# SCH_SrProj_v1_6_final.net
KiCad netlist of a schematic drawn in EasyEDA
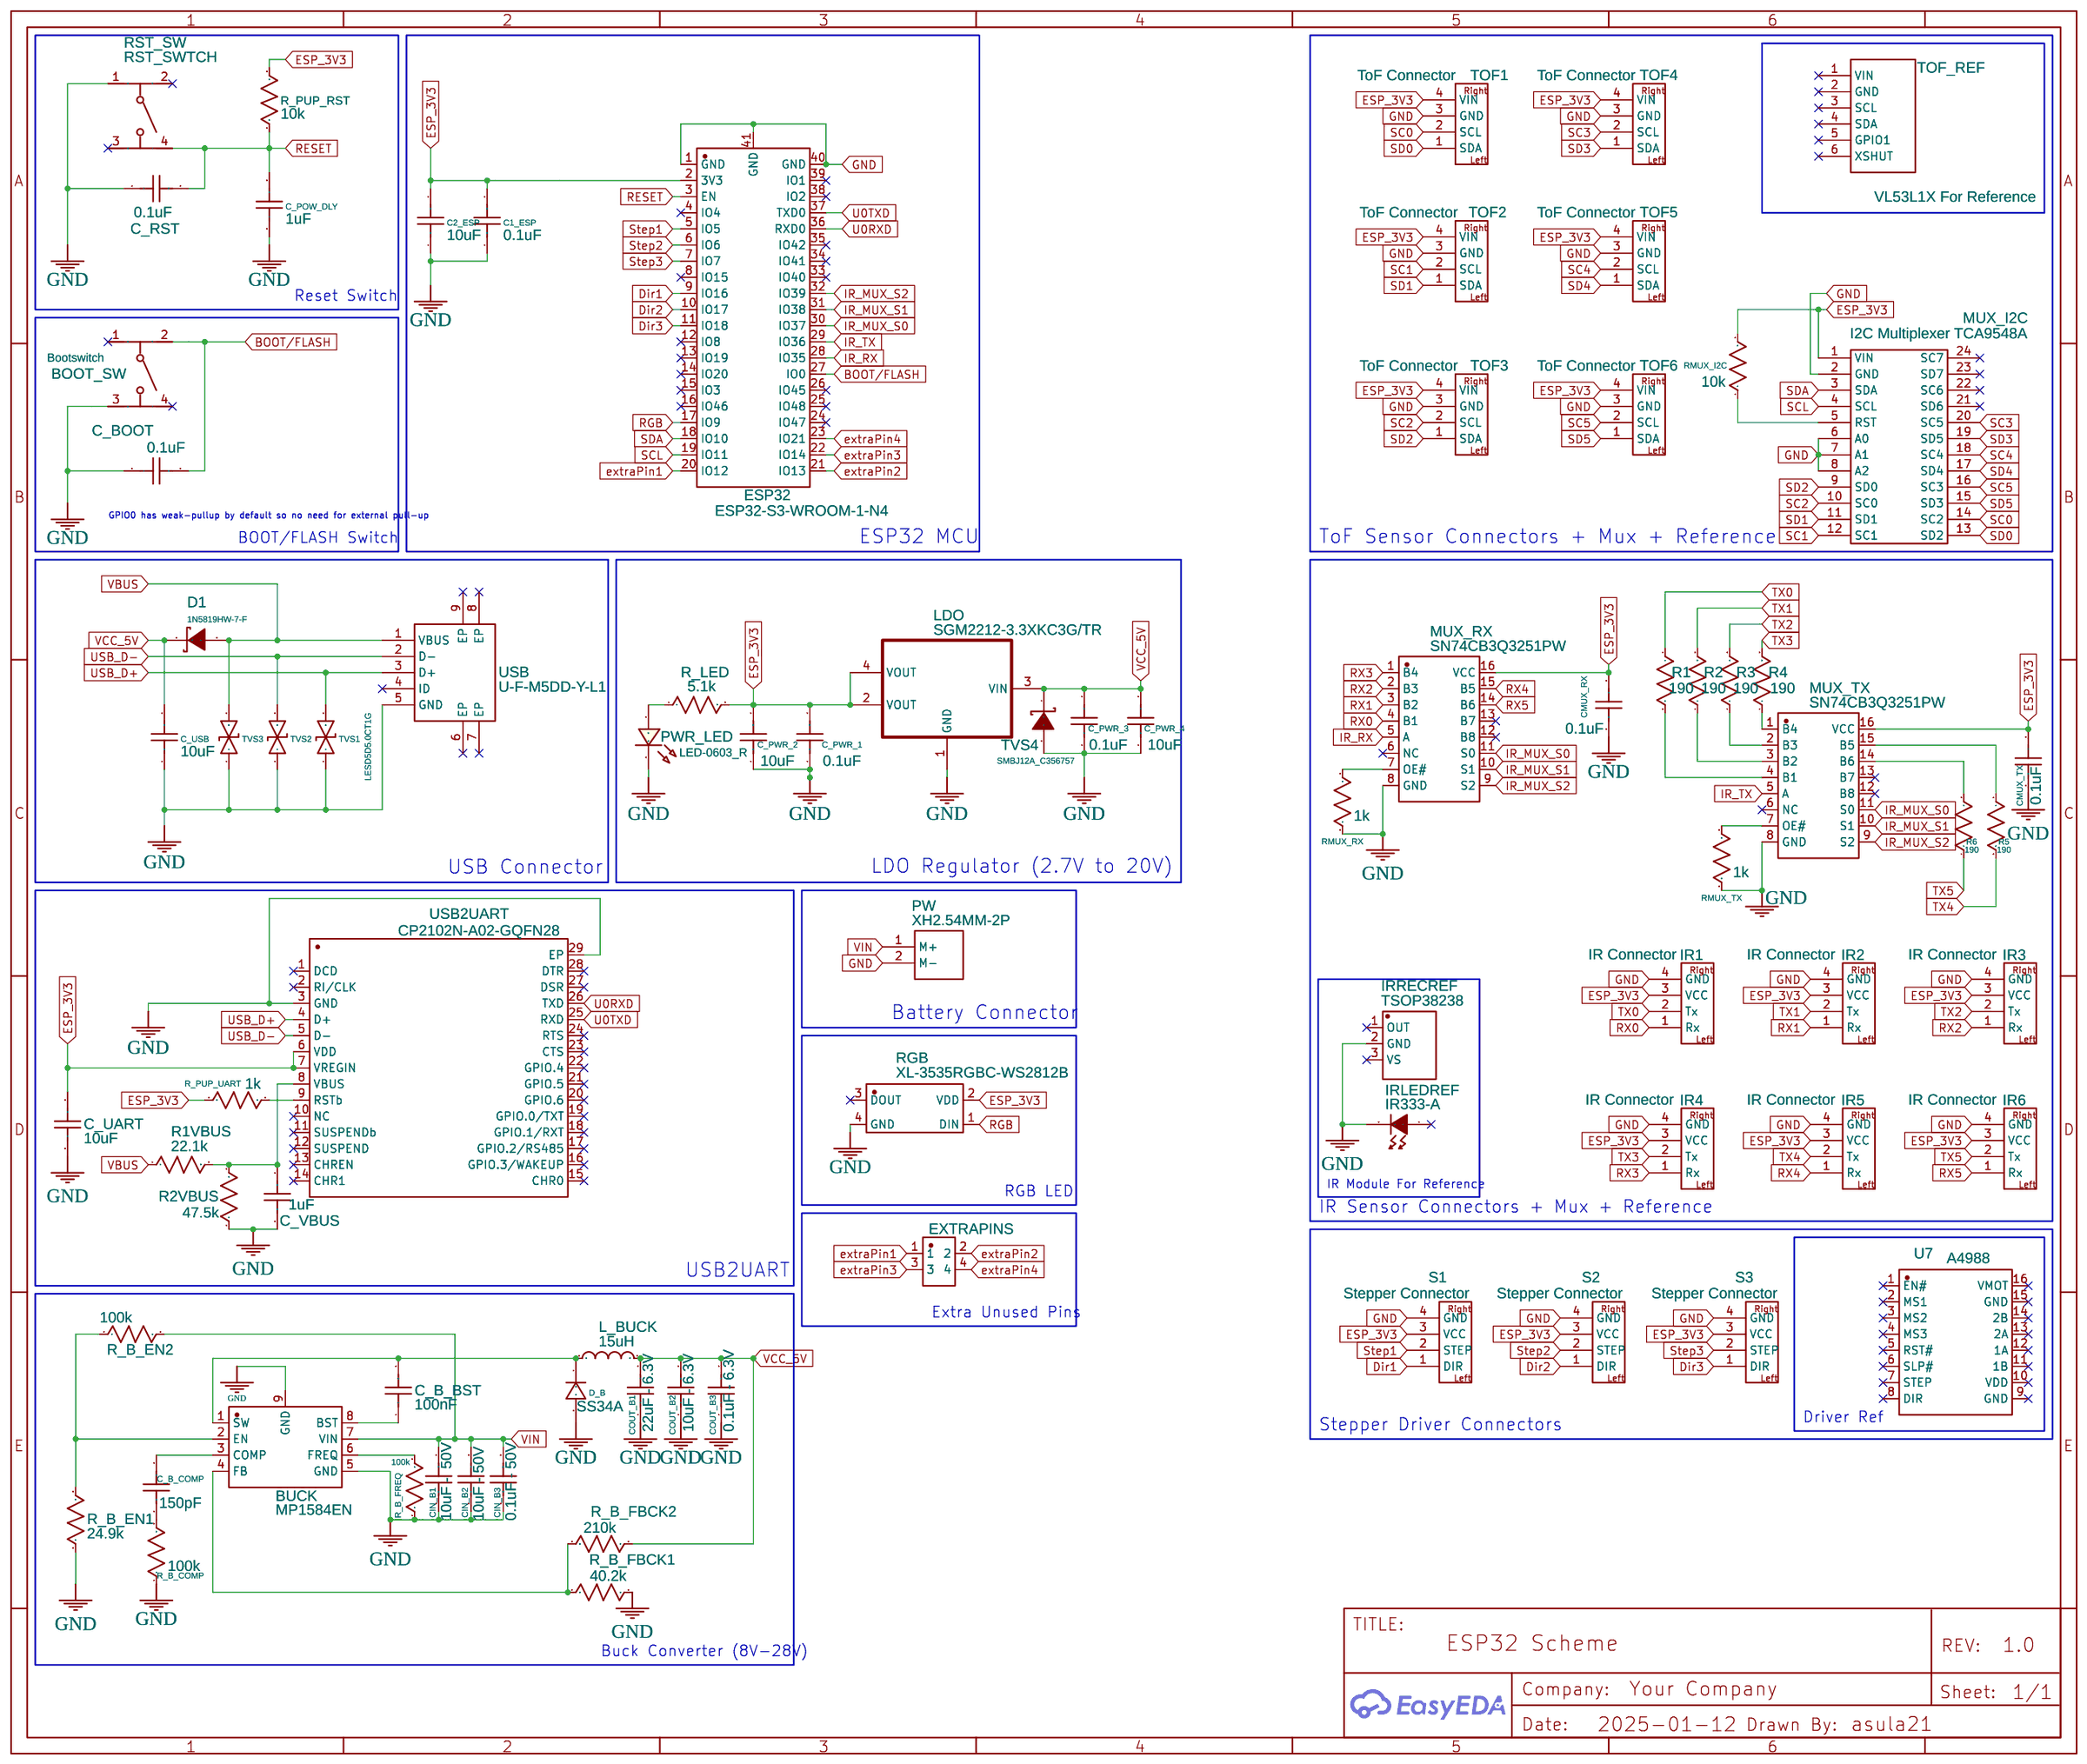
[diagram p0: schematic sheet]

(export (version "E")
  (design (tool "Eeschema 10.0.6"))
  (components
    (comp (ref "BOOT_SW")
      (value "Bootswitch")
      (fields
        (field (name "Manufacturer Part") "Switch,6*6*6Plastic head,260G, 0.25mm,Straight line")
        (field (name "Manufacturer") "BBJ")
      )
      (libsource (lib "") (part "Button-6x6x6mm"))
    )
    (comp (ref "BUCK") (value "MP1584EN") (libsource (lib "") (part "MP1584EN")))
    (comp (ref "C1_ESP") (value "0.1uF") (libsource (lib "") (part "C_0603_US_8")))
    (comp (ref "C2_ESP") (value "10uF") (libsource (lib "") (part "C_0603_US_1")))
    (comp (ref "CIN_B1") (value "10uF -  50V") (libsource (lib "") (part "C_0603_US_7")))
    (comp (ref "CIN_B2") (value "10uF - 50V") (libsource (lib "") (part "C_0603_US_7")))
    (comp (ref "CIN_B3") (value "0.1uF - 50V") (libsource (lib "") (part "C_0603_US_7")))
    (comp (ref "CMUX_RX") (value "0.1uF") (libsource (lib "") (part "C_0603_US_11")))
    (comp (ref "CMUX_TX") (value "0.1uF") (libsource (lib "") (part "C_0603_US_12")))
    (comp (ref "COUT_B1") (value "22uF - 6.3V") (libsource (lib "") (part "C_0603_US_3")))
    (comp (ref "COUT_B2") (value "10uF - 6.3V") (libsource (lib "") (part "C_0603_US_3")))
    (comp (ref "COUT_B3") (value "0.1uF - 6.3V") (libsource (lib "") (part "C_0603_US_3")))
    (comp (ref "C_BOOT") (value "0.1uF") (libsource (lib "") (part "C_0603_US_5")))
    (comp (ref "C_B_BST") (value "100nF") (libsource (lib "") (part "C_0603_US")))
    (comp (ref "C_B_COMP") (value "150pF") (libsource (lib "") (part "C_0603_US_6")))
    (comp (ref "C_POW_DLY") (value "1uF") (libsource (lib "") (part "C_0603_US_14")))
    (comp (ref "C_PWR_1") (value "0.1uF") (libsource (lib "") (part "C_0603_US_4")))
    (comp (ref "C_PWR_2") (value "10uF") (libsource (lib "") (part "C_0603_US_4")))
    (comp (ref "C_PWR_3") (value "0.1uF") (libsource (lib "") (part "C_0603_US_4")))
    (comp (ref "C_PWR_4") (value "10uF") (libsource (lib "") (part "C_0603_US_4")))
    (comp (ref "C_RST") (value "0.1uF") (libsource (lib "") (part "C_0603_US_10")))
    (comp (ref "C_UART") (value "10uF") (libsource (lib "") (part "C_0603_US_13")))
    (comp (ref "C_USB") (value "10uF") (libsource (lib "") (part "C_0603_US_2")))
    (comp (ref "C_VBUS") (value "1uF") (libsource (lib "") (part "C_0603_US_9")))
    (comp (ref "D1")
      (value "1N5819HW-7-F")
      (fields (field (name "Manufacturer") "DIODES(美台)"))
      (libsource (lib "") (part "1N5819HW-7-F"))
    )
    (comp (ref "D_B")
      (value "SS34A")
      (fields (field (name "Manufacturer") "YANGJIE(扬杰)"))
      (libsource (lib "") (part "SS34A"))
    )
    (comp (ref "ESP32")
      (value "ESP32-S3-WROOM-1-N4")
      (fields (field (name "Manufacturer") "ESPRESSIF(乐鑫)"))
      (libsource (lib "") (part "ESP32-S3-WROOM-1-N4"))
    )
    (comp (ref "EXTRAPINS")
      (value "排母/2.54MM2X2直排母袋装环保")
      (fields
        (field (name "Manufacturer Part") "排母/2.54mm2x2直排母袋装环保")
        (field (name "Manufacturer") "BOOMELE(博穆精密)")
      )
      (libsource (lib "") (part "排母/2.54MM2X2直排母袋装环保"))
    )
    (comp (ref "IR1") (value "IR Connector") (libsource (lib "") (part "MY XH2.54MM.4P_1")))
    (comp (ref "IR2") (value "IR Connector") (libsource (lib "") (part "MY XH2.54MM.4P_1")))
    (comp (ref "IR3") (value "IR Connector") (libsource (lib "") (part "MY XH2.54MM.4P_1")))
    (comp (ref "IR4") (value "IR Connector") (libsource (lib "") (part "MY XH2.54MM.4P_1")))
    (comp (ref "IR5") (value "IR Connector") (libsource (lib "") (part "MY XH2.54MM.4P_1")))
    (comp (ref "IR6") (value "IR Connector") (libsource (lib "") (part "MY XH2.54MM.4P_1")))
    (comp (ref "IRLEDREF")
      (value "IR333-A")
      (fields (field (name "Manufacturer") "EVERLIGHT(亿光)"))
      (libsource (lib "") (part "IR333-A"))
    )
    (comp (ref "IRRECREF")
      (value "TSOP38238")
      (fields (field (name "Manufacturer") "VISHAY(威世)"))
      (libsource (lib "") (part "TSOP38238"))
    )
    (comp (ref "LDO") (value "SGM2212-3.3XKC3G/TR") (libsource (lib "") (part "SGM2212-3.3XKC3G/TR")))
    (comp (ref "L_BUCK")
      (value "15uH")
      (fields (field (name "Manufacturer Part") "CYA1040-15UH") (field (name "Manufacturer") "SHOU HAN(首韩)"))
      (libsource (lib "") (part "CYA1040-15UH"))
    )
    (comp (ref "MUX_I2C")
      (value "I2C Multiplexer TCA9548A")
      (fields (field (name "Manufacturer Part") "IDSN-TCA9548A") (field (name "Manufacturer") "IDSN"))
      (libsource (lib "") (part "TCA9548A I2C MULTIPLEXER 8 CHANEL"))
    )
    (comp (ref "MUX_RX")
      (value "SN74CB3Q3251PW")
      (fields (field (name "Manufacturer") "TI(德州仪器)"))
      (libsource (lib "") (part "SN74CB3Q3251PW"))
    )
    (comp (ref "MUX_TX")
      (value "SN74CB3Q3251PW")
      (fields (field (name "Manufacturer") "TI(德州仪器)"))
      (libsource (lib "") (part "SN74CB3Q3251PW_1"))
    )
    (comp (ref "PW")
      (value "XH2.54MM-2P")
      (fields (field (name "Manufacturer Part") "Header P2 PH2.0 TUANLE"))
      (libsource (lib "") (part "PH2.0-2P"))
    )
    (comp (ref "PWR_LED")
      (value "LED-0603_R")
      (fields
        (field (name "Manufacturer Part") "19-217/R6C-AL1M2VY/3T")
        (field (name "Manufacturer") "EVERLIGHT(台湾亿光)")
      )
      (libsource (lib "") (part "LED-0603_R"))
    )
    (comp (ref "R1") (value "190") (libsource (lib "") (part "R_0805_US_1")))
    (comp (ref "R1VBUS") (value "22.1k") (libsource (lib "") (part "R_0603_US_9")))
    (comp (ref "R2") (value "190") (libsource (lib "") (part "R_0805_US")))
    (comp (ref "R2VBUS") (value "47.5k") (libsource (lib "") (part "R_0603_US_1")))
    (comp (ref "R3") (value "190") (libsource (lib "") (part "R_0805_US")))
    (comp (ref "R4") (value "190") (libsource (lib "") (part "R_0805_US")))
    (comp (ref "R5") (value "190") (libsource (lib "") (part "R_0805_US_1")))
    (comp (ref "R6") (value "190") (libsource (lib "") (part "R_0805_US")))
    (comp (ref "RGB")
      (value "XL-3535RGBC-WS2812B")
      (fields (field (name "Manufacturer") "XINGLIGHT(成兴光)"))
      (libsource (lib "") (part "XL-3535RGBC-WS2812B"))
    )
    (comp (ref "RMUX_I2C") (value "10k") (libsource (lib "") (part "R_0603_US_12")))
    (comp (ref "RMUX_RX") (value "1k") (libsource (lib "") (part "R_0603_US_13")))
    (comp (ref "RMUX_TX") (value "1k") (libsource (lib "") (part "R_0603_US_11")))
    (comp (ref "RST_SW")
      (value "RST_SWTCH")
      (fields
        (field (name "Manufacturer Part") "Switch,6*6*6Plastic head,260G, 0.25mm,Straight line")
        (field (name "Manufacturer") "BBJ")
      )
      (libsource (lib "") (part "Button-6x6x6mm_1"))
    )
    (comp (ref "R_B_COMP") (value "100k") (libsource (lib "") (part "R_0603_US_5")))
    (comp (ref "R_B_EN1") (value "24.9k") (libsource (lib "") (part "R_0603_US_4")))
    (comp (ref "R_B_EN2") (value "100k") (libsource (lib "") (part "R_0603_US")))
    (comp (ref "R_B_FBCK1") (value "40.2k") (libsource (lib "") (part "R_0603_US_3")))
    (comp (ref "R_B_FBCK2") (value "210k") (libsource (lib "") (part "R_0603_US_8")))
    (comp (ref "R_B_FREQ") (value "100k") (libsource (lib "") (part "R_0603_US_10")))
    (comp (ref "R_LED") (value "5.1k") (libsource (lib "") (part "R_0603_US_7")))
    (comp (ref "R_PUP_RST") (value "10k") (libsource (lib "") (part "R_0603_US_2")))
    (comp (ref "R_PUP_UART") (value "1k") (libsource (lib "") (part "R_0603_US_6")))
    (comp (ref "S1") (value "Stepper Connector") (libsource (lib "") (part "MY XH2.54MM.4P")))
    (comp (ref "S2") (value "Stepper Connector") (libsource (lib "") (part "MY XH2.54MM.4P")))
    (comp (ref "S3") (value "Stepper Connector") (libsource (lib "") (part "MY XH2.54MM.4P")))
    (comp (ref "TOF1") (value "ToF Connector") (libsource (lib "") (part "MY XH2.54MM.4P_2")))
    (comp (ref "TOF2") (value "ToF Connector") (libsource (lib "") (part "MY XH2.54MM.4P_2")))
    (comp (ref "TOF3") (value "ToF Connector") (libsource (lib "") (part "MY XH2.54MM.4P_2")))
    (comp (ref "TOF4") (value "ToF Connector") (libsource (lib "") (part "MY XH2.54MM.4P_2")))
    (comp (ref "TOF5") (value "ToF Connector") (libsource (lib "") (part "MY XH2.54MM.4P_2")))
    (comp (ref "TOF6") (value "ToF Connector") (libsource (lib "") (part "MY XH2.54MM.4P_2")))
    (comp (ref "TOF_REF")
      (value "VL53L1X For Reference")
      (fields (field (name "Manufacturer Part") "VL53L0X Time-of-Flight Distance Sensor VL53L0X"))
      (libsource (lib "") (part "VL53L1X_BREAKOUT"))
    )
    (comp (ref "TVS1")
      (value "LESD5D5.0CT1G")
      (fields (field (name "Manufacturer") "LRC(乐山无线电)"))
      (libsource (lib "") (part "LESD5D5.0CT1G"))
    )
    (comp (ref "TVS2")
      (value "LESD5D5.0CT1G")
      (fields (field (name "Manufacturer") "LRC(乐山无线电)"))
      (libsource (lib "") (part "LESD5D5.0CT1G"))
    )
    (comp (ref "TVS3")
      (value "LESD5D5.0CT1G")
      (fields (field (name "Manufacturer") "LRC(乐山无线电)"))
      (libsource (lib "") (part "LESD5D5.0CT1G"))
    )
    (comp (ref "TVS4")
      (value "SMBJ12A_C356757")
      (fields (field (name "Manufacturer Part") "SMBJ12A") (field (name "Manufacturer") "JJW(捷捷微)"))
      (libsource (lib "") (part "SMBJ12A_C356757"))
    )
    (comp (ref "U7") (value "A4988") (libsource (lib "") (part "A4988")))
    (comp (ref "USB")
      (value "U-F-M5DD-Y-L1")
      (fields (field (name "Manufacturer") "韩国韩荣"))
      (libsource (lib "") (part "U-F-M5DD-Y-L1"))
    )
    (comp (ref "USB2UART")
      (value "CP2102N-A02-GQFN28")
      (fields (field (name "Manufacturer") "SKYWORKS/SILICON LABS(芯科)"))
      (libsource (lib "") (part "CP2102N-A02-GQFN28"))
    )
  )
  (nets
    (net (code "1") (name "BOOT{slash}FLASH") (class "Default")
      (node (ref "BOOT_SW") (pin "2") (pinfunction "2_2") (pintype "unspecified"))
      (node (ref "C_BOOT") (pin "2") (pinfunction "2_2") (pintype "unspecified"))
      (node (ref "ESP32") (pin "27") (pinfunction "IO0_27") (pintype "unspecified"))
    )
    (net (code "2") (name "Dir1") (class "Default")
      (node (ref "ESP32") (pin "9") (pinfunction "IO16_9") (pintype "unspecified"))
      (node (ref "S1") (pin "1") (pinfunction "DIR_1") (pintype "unspecified"))
    )
    (net (code "3") (name "Dir2") (class "Default")
      (node (ref "ESP32") (pin "10") (pinfunction "IO17_10") (pintype "unspecified"))
      (node (ref "S2") (pin "1") (pinfunction "DIR_1") (pintype "unspecified"))
    )
    (net (code "4") (name "Dir3") (class "Default")
      (node (ref "ESP32") (pin "11") (pinfunction "IO18_11") (pintype "unspecified"))
      (node (ref "S3") (pin "1") (pinfunction "DIR_1") (pintype "unspecified"))
    )
    (net (code "5") (name "ESP_3V3") (class "Default")
      (node (ref "C1_ESP") (pin "2") (pinfunction "2_2") (pintype "unspecified"))
      (node (ref "C2_ESP") (pin "2") (pinfunction "2_2") (pintype "unspecified"))
      (node (ref "CMUX_RX") (pin "2") (pinfunction "2_2") (pintype "unspecified"))
      (node (ref "CMUX_TX") (pin "2") (pinfunction "2_2") (pintype "unspecified"))
      (node (ref "C_PWR_1") (pin "2") (pinfunction "2_2") (pintype "unspecified"))
      (node (ref "C_PWR_2") (pin "2") (pinfunction "2_2") (pintype "unspecified"))
      (node (ref "C_UART") (pin "2") (pinfunction "2_2") (pintype "unspecified"))
      (node (ref "ESP32") (pin "2") (pinfunction "3V3_2") (pintype "unspecified"))
      (node (ref "IR1") (pin "3") (pinfunction "VCC_3") (pintype "unspecified"))
      (node (ref "IR2") (pin "3") (pinfunction "VCC_3") (pintype "unspecified"))
      (node (ref "IR3") (pin "3") (pinfunction "VCC_3") (pintype "unspecified"))
      (node (ref "IR4") (pin "3") (pinfunction "VCC_3") (pintype "unspecified"))
      (node (ref "IR5") (pin "3") (pinfunction "VCC_3") (pintype "unspecified"))
      (node (ref "IR6") (pin "3") (pinfunction "VCC_3") (pintype "unspecified"))
      (node (ref "LDO") (pin "2") (pinfunction "VOUT_2") (pintype "unspecified"))
      (node (ref "LDO") (pin "4") (pinfunction "VOUT_4") (pintype "unspecified"))
      (node (ref "MUX_I2C") (pin "1") (pinfunction "VIN_1") (pintype "unspecified"))
      (node (ref "MUX_RX") (pin "16") (pinfunction "VCC_16") (pintype "unspecified"))
      (node (ref "MUX_TX") (pin "16") (pinfunction "VCC_16") (pintype "unspecified"))
      (node (ref "RGB") (pin "2") (pinfunction "VDD_2") (pintype "unspecified"))
      (node (ref "RMUX_I2C") (pin "2") (pinfunction "2_2") (pintype "unspecified"))
      (node (ref "R_LED") (pin "2") (pinfunction "2_2") (pintype "unspecified"))
      (node (ref "R_PUP_RST") (pin "2") (pinfunction "2_2") (pintype "unspecified"))
      (node (ref "R_PUP_UART") (pin "2") (pinfunction "2_2") (pintype "unspecified"))
      (node (ref "S1") (pin "3") (pinfunction "VCC_3") (pintype "unspecified"))
      (node (ref "S2") (pin "3") (pinfunction "VCC_3") (pintype "unspecified"))
      (node (ref "S3") (pin "3") (pinfunction "VCC_3") (pintype "unspecified"))
      (node (ref "TOF1") (pin "4") (pinfunction "VIN_4") (pintype "unspecified"))
      (node (ref "TOF2") (pin "4") (pinfunction "VIN_4") (pintype "unspecified"))
      (node (ref "TOF3") (pin "4") (pinfunction "VIN_4") (pintype "unspecified"))
      (node (ref "TOF4") (pin "4") (pinfunction "VIN_4") (pintype "unspecified"))
      (node (ref "TOF5") (pin "4") (pinfunction "VIN_4") (pintype "unspecified"))
      (node (ref "TOF6") (pin "4") (pinfunction "VIN_4") (pintype "unspecified"))
      (node (ref "USB2UART") (pin "6") (pinfunction "VDD_6") (pintype "unspecified"))
      (node (ref "USB2UART") (pin "7") (pinfunction "VREGIN_7") (pintype "unspecified"))
    )
    (net (code "6") (name "GND") (class "Default")
      (node (ref "BOOT_SW") (pin "3") (pinfunction "3_3") (pintype "unspecified"))
      (node (ref "BUCK") (pin "5") (pinfunction "GND_5") (pintype "unspecified"))
      (node (ref "BUCK") (pin "9") (pinfunction "GND_9") (pintype "unspecified"))
      (node (ref "C1_ESP") (pin "1") (pinfunction "1_1") (pintype "unspecified"))
      (node (ref "C2_ESP") (pin "1") (pinfunction "1_1") (pintype "unspecified"))
      (node (ref "CIN_B1") (pin "1") (pinfunction "1_1") (pintype "unspecified"))
      (node (ref "CIN_B2") (pin "1") (pinfunction "1_1") (pintype "unspecified"))
      (node (ref "CIN_B3") (pin "1") (pinfunction "1_1") (pintype "unspecified"))
      (node (ref "CMUX_RX") (pin "1") (pinfunction "1_1") (pintype "unspecified"))
      (node (ref "CMUX_TX") (pin "1") (pinfunction "1_1") (pintype "unspecified"))
      (node (ref "COUT_B1") (pin "1") (pinfunction "1_1") (pintype "unspecified"))
      (node (ref "COUT_B2") (pin "1") (pinfunction "1_1") (pintype "unspecified"))
      (node (ref "COUT_B3") (pin "1") (pinfunction "1_1") (pintype "unspecified"))
      (node (ref "C_BOOT") (pin "1") (pinfunction "1_1") (pintype "unspecified"))
      (node (ref "C_POW_DLY") (pin "1") (pinfunction "1_1") (pintype "unspecified"))
      (node (ref "C_PWR_1") (pin "1") (pinfunction "1_1") (pintype "unspecified"))
      (node (ref "C_PWR_2") (pin "1") (pinfunction "1_1") (pintype "unspecified"))
      (node (ref "C_PWR_3") (pin "1") (pinfunction "1_1") (pintype "unspecified"))
      (node (ref "C_PWR_4") (pin "1") (pinfunction "1_1") (pintype "unspecified"))
      (node (ref "C_RST") (pin "1") (pinfunction "1_1") (pintype "unspecified"))
      (node (ref "C_UART") (pin "1") (pinfunction "1_1") (pintype "unspecified"))
      (node (ref "C_USB") (pin "1") (pinfunction "1_1") (pintype "unspecified"))
      (node (ref "C_VBUS") (pin "2") (pinfunction "2_2") (pintype "unspecified"))
      (node (ref "D_B") (pin "2") (pinfunction "A_2") (pintype "unspecified"))
      (node (ref "ESP32") (pin "1") (pinfunction "GND_1") (pintype "unspecified"))
      (node (ref "ESP32") (pin "40") (pinfunction "GND_40") (pintype "unspecified"))
      (node (ref "ESP32") (pin "41") (pinfunction "GND_41") (pintype "unspecified"))
      (node (ref "IR1") (pin "4") (pinfunction "GND_4") (pintype "unspecified"))
      (node (ref "IR2") (pin "4") (pinfunction "GND_4") (pintype "unspecified"))
      (node (ref "IR3") (pin "4") (pinfunction "GND_4") (pintype "unspecified"))
      (node (ref "IR4") (pin "4") (pinfunction "GND_4") (pintype "unspecified"))
      (node (ref "IR5") (pin "4") (pinfunction "GND_4") (pintype "unspecified"))
      (node (ref "IR6") (pin "4") (pinfunction "GND_4") (pintype "unspecified"))
      (node (ref "IRLEDREF") (pin "2") (pinfunction "C_2") (pintype "input"))
      (node (ref "IRRECREF") (pin "2") (pinfunction "GND_2") (pintype "unspecified"))
      (node (ref "LDO") (pin "1") (pinfunction "GND_1") (pintype "unspecified"))
      (node (ref "MUX_I2C") (pin "2") (pinfunction "GND_2") (pintype "unspecified"))
      (node (ref "MUX_I2C") (pin "6") (pinfunction "A0_6") (pintype "unspecified"))
      (node (ref "MUX_I2C") (pin "7") (pinfunction "A1_7") (pintype "unspecified"))
      (node (ref "MUX_I2C") (pin "8") (pinfunction "A2_8") (pintype "unspecified"))
      (node (ref "MUX_RX") (pin "8") (pinfunction "GND_8") (pintype "unspecified"))
      (node (ref "MUX_TX") (pin "8") (pinfunction "GND_8") (pintype "unspecified"))
      (node (ref "PW") (pin "2") (pinfunction "M-_2") (pintype "unspecified"))
      (node (ref "PWR_LED") (pin "2") (pinfunction "2_2") (pintype "unspecified"))
      (node (ref "R2VBUS") (pin "1") (pinfunction "1_1") (pintype "unspecified"))
      (node (ref "RGB") (pin "4") (pinfunction "GND_4") (pintype "unspecified"))
      (node (ref "RMUX_RX") (pin "1") (pinfunction "1_1") (pintype "unspecified"))
      (node (ref "RMUX_TX") (pin "1") (pinfunction "1_1") (pintype "unspecified"))
      (node (ref "RST_SW") (pin "1") (pinfunction "1_1") (pintype "unspecified"))
      (node (ref "R_B_COMP") (pin "1") (pinfunction "1_1") (pintype "unspecified"))
      (node (ref "R_B_EN1") (pin "1") (pinfunction "1_1") (pintype "unspecified"))
      (node (ref "R_B_FBCK1") (pin "2") (pinfunction "2_2") (pintype "unspecified"))
      (node (ref "R_B_FREQ") (pin "1") (pinfunction "1_1") (pintype "unspecified"))
      (node (ref "S1") (pin "4") (pinfunction "GND_4") (pintype "unspecified"))
      (node (ref "S2") (pin "4") (pinfunction "GND_4") (pintype "unspecified"))
      (node (ref "S3") (pin "4") (pinfunction "GND_4") (pintype "unspecified"))
      (node (ref "TOF1") (pin "3") (pinfunction "GND_3") (pintype "unspecified"))
      (node (ref "TOF2") (pin "3") (pinfunction "GND_3") (pintype "unspecified"))
      (node (ref "TOF3") (pin "3") (pinfunction "GND_3") (pintype "unspecified"))
      (node (ref "TOF4") (pin "3") (pinfunction "GND_3") (pintype "unspecified"))
      (node (ref "TOF5") (pin "3") (pinfunction "GND_3") (pintype "unspecified"))
      (node (ref "TOF6") (pin "3") (pinfunction "GND_3") (pintype "unspecified"))
      (node (ref "TVS1") (pin "1") (pinfunction "1_1") (pintype "unspecified"))
      (node (ref "TVS2") (pin "1") (pinfunction "1_1") (pintype "unspecified"))
      (node (ref "TVS3") (pin "1") (pinfunction "1_1") (pintype "unspecified"))
      (node (ref "TVS4") (pin "2") (pinfunction "A_2") (pintype "unspecified"))
      (node (ref "USB") (pin "5") (pinfunction "GND_5") (pintype "unspecified"))
      (node (ref "USB2UART") (pin "29") (pinfunction "EP_29") (pintype "unspecified"))
      (node (ref "USB2UART") (pin "3") (pinfunction "GND_3") (pintype "unspecified"))
    )
    (net (code "7") (name "IR_MUX_S0") (class "Default")
      (node (ref "ESP32") (pin "30") (pinfunction "IO37_30") (pintype "unspecified"))
      (node (ref "MUX_RX") (pin "11") (pinfunction "S0_11") (pintype "unspecified"))
      (node (ref "MUX_TX") (pin "11") (pinfunction "S0_11") (pintype "unspecified"))
    )
    (net (code "8") (name "IR_MUX_S1") (class "Default")
      (node (ref "ESP32") (pin "31") (pinfunction "IO38_31") (pintype "unspecified"))
      (node (ref "MUX_RX") (pin "10") (pinfunction "S1_10") (pintype "unspecified"))
      (node (ref "MUX_TX") (pin "10") (pinfunction "S1_10") (pintype "unspecified"))
    )
    (net (code "9") (name "IR_MUX_S2") (class "Default")
      (node (ref "ESP32") (pin "32") (pinfunction "IO39_32") (pintype "unspecified"))
      (node (ref "MUX_RX") (pin "9") (pinfunction "S2_9") (pintype "unspecified"))
      (node (ref "MUX_TX") (pin "9") (pinfunction "S2_9") (pintype "unspecified"))
    )
    (net (code "10") (name "IR_RX") (class "Default")
      (node (ref "ESP32") (pin "28") (pinfunction "IO35_28") (pintype "unspecified"))
      (node (ref "MUX_RX") (pin "5") (pinfunction "A_5") (pintype "unspecified"))
    )
    (net (code "11") (name "IR_TX") (class "Default")
      (node (ref "ESP32") (pin "29") (pinfunction "IO36_29") (pintype "unspecified"))
      (node (ref "MUX_TX") (pin "5") (pinfunction "A_5") (pintype "unspecified"))
    )
    (net (code "12") (name "Net-(BUCK-BST)") (class "Default")
      (node (ref "BUCK") (pin "8") (pinfunction "BST_8") (pintype "unspecified"))
      (node (ref "C_B_BST") (pin "1") (pinfunction "1_1") (pintype "unspecified"))
    )
    (net (code "13") (name "Net-(BUCK-COMP)") (class "Default")
      (node (ref "BUCK") (pin "3") (pinfunction "COMP_3") (pintype "unspecified"))
      (node (ref "C_B_COMP") (pin "2") (pinfunction "2_2") (pintype "unspecified"))
    )
    (net (code "14") (name "Net-(BUCK-EN)") (class "Default")
      (node (ref "BUCK") (pin "2") (pinfunction "EN_2") (pintype "unspecified"))
      (node (ref "R_B_EN1") (pin "2") (pinfunction "2_2") (pintype "unspecified"))
      (node (ref "R_B_EN2") (pin "1") (pinfunction "1_1") (pintype "unspecified"))
    )
    (net (code "15") (name "Net-(BUCK-FB)") (class "Default")
      (node (ref "BUCK") (pin "4") (pinfunction "FB_4") (pintype "unspecified"))
      (node (ref "R_B_FBCK1") (pin "1") (pinfunction "1_1") (pintype "unspecified"))
      (node (ref "R_B_FBCK2") (pin "2") (pinfunction "2_2") (pintype "unspecified"))
    )
    (net (code "16") (name "Net-(BUCK-FREQ)") (class "Default")
      (node (ref "BUCK") (pin "6") (pinfunction "FREQ_6") (pintype "unspecified"))
      (node (ref "R_B_FREQ") (pin "2") (pinfunction "2_2") (pintype "unspecified"))
    )
    (net (code "17") (name "Net-(BUCK-SW)") (class "Default")
      (node (ref "BUCK") (pin "1") (pinfunction "SW_1") (pintype "unspecified"))
      (node (ref "C_B_BST") (pin "2") (pinfunction "2_2") (pintype "unspecified"))
      (node (ref "D_B") (pin "1") (pinfunction "C_1") (pintype "unspecified"))
      (node (ref "L_BUCK") (pin "1") (pinfunction "1_1") (pintype "unspecified"))
    )
    (net (code "18") (name "Net-(C_B_COMP-Pad1)") (class "Default")
      (node (ref "C_B_COMP") (pin "1") (pinfunction "1_1") (pintype "unspecified"))
      (node (ref "R_B_COMP") (pin "2") (pinfunction "2_2") (pintype "unspecified"))
    )
    (net (code "19") (name "Net-(MUX_I2C-RST)") (class "Default")
      (node (ref "MUX_I2C") (pin "5") (pinfunction "RST_5") (pintype "unspecified"))
      (node (ref "RMUX_I2C") (pin "1") (pinfunction "1_1") (pintype "unspecified"))
    )
    (net (code "20") (name "Net-(MUX_RX-OE#)") (class "Default")
      (node (ref "MUX_RX") (pin "7") (pinfunction "OE#_7") (pintype "unspecified"))
      (node (ref "RMUX_RX") (pin "2") (pinfunction "2_2") (pintype "unspecified"))
    )
    (net (code "21") (name "Net-(MUX_TX-B1)") (class "Default")
      (node (ref "MUX_TX") (pin "4") (pinfunction "B1_4") (pintype "unspecified"))
      (node (ref "R1") (pin "2") (pinfunction "2_2") (pintype "unspecified"))
    )
    (net (code "22") (name "Net-(MUX_TX-B2)") (class "Default")
      (node (ref "MUX_TX") (pin "3") (pinfunction "B2_3") (pintype "unspecified"))
      (node (ref "R2") (pin "1") (pinfunction "1_1") (pintype "unspecified"))
    )
    (net (code "23") (name "Net-(MUX_TX-B3)") (class "Default")
      (node (ref "MUX_TX") (pin "2") (pinfunction "B3_2") (pintype "unspecified"))
      (node (ref "R3") (pin "1") (pinfunction "1_1") (pintype "unspecified"))
    )
    (net (code "24") (name "Net-(MUX_TX-B4)") (class "Default")
      (node (ref "MUX_TX") (pin "1") (pinfunction "B4_1") (pintype "unspecified"))
      (node (ref "R4") (pin "1") (pinfunction "1_1") (pintype "unspecified"))
    )
    (net (code "25") (name "Net-(MUX_TX-B5)") (class "Default")
      (node (ref "MUX_TX") (pin "15") (pinfunction "B5_15") (pintype "unspecified"))
      (node (ref "R5") (pin "1") (pinfunction "1_1") (pintype "unspecified"))
    )
    (net (code "26") (name "Net-(MUX_TX-B6)") (class "Default")
      (node (ref "MUX_TX") (pin "14") (pinfunction "B6_14") (pintype "unspecified"))
      (node (ref "R6") (pin "2") (pinfunction "2_2") (pintype "unspecified"))
    )
    (net (code "27") (name "Net-(MUX_TX-OE#)") (class "Default")
      (node (ref "MUX_TX") (pin "7") (pinfunction "OE#_7") (pintype "unspecified"))
      (node (ref "RMUX_TX") (pin "2") (pinfunction "2_2") (pintype "unspecified"))
    )
    (net (code "28") (name "Net-(PWR_LED-Pad1)") (class "Default")
      (node (ref "PWR_LED") (pin "1") (pinfunction "1_1") (pintype "unspecified"))
      (node (ref "R_LED") (pin "1") (pinfunction "1_1") (pintype "unspecified"))
    )
    (net (code "29") (name "Net-(USB2UART-RSTb)") (class "Default")
      (node (ref "R_PUP_UART") (pin "1") (pinfunction "1_1") (pintype "unspecified"))
      (node (ref "USB2UART") (pin "9") (pinfunction "RSTb_9") (pintype "unspecified"))
    )
    (net (code "30") (name "Net-(USB2UART-VBUS)") (class "Default")
      (node (ref "C_VBUS") (pin "1") (pinfunction "1_1") (pintype "unspecified"))
      (node (ref "R1VBUS") (pin "2") (pinfunction "2_2") (pintype "unspecified"))
      (node (ref "R2VBUS") (pin "2") (pinfunction "2_2") (pintype "unspecified"))
      (node (ref "USB2UART") (pin "8") (pinfunction "VBUS_8") (pintype "unspecified"))
    )
    (net (code "31") (name "RESET") (class "Default")
      (node (ref "C_POW_DLY") (pin "2") (pinfunction "2_2") (pintype "unspecified"))
      (node (ref "C_RST") (pin "2") (pinfunction "2_2") (pintype "unspecified"))
      (node (ref "ESP32") (pin "3") (pinfunction "EN_3") (pintype "unspecified"))
      (node (ref "RST_SW") (pin "4") (pinfunction "4_4") (pintype "unspecified"))
      (node (ref "R_PUP_RST") (pin "1") (pinfunction "1_1") (pintype "unspecified"))
    )
    (net (code "32") (name "RGB") (class "Default")
      (node (ref "ESP32") (pin "17") (pinfunction "IO9_17") (pintype "unspecified"))
      (node (ref "RGB") (pin "1") (pinfunction "DIN_1") (pintype "unspecified"))
    )
    (net (code "33") (name "RX0") (class "Default")
      (node (ref "IR1") (pin "1") (pinfunction "Rx_1") (pintype "unspecified"))
      (node (ref "MUX_RX") (pin "4") (pinfunction "B1_4") (pintype "unspecified"))
    )
    (net (code "34") (name "RX1") (class "Default")
      (node (ref "IR2") (pin "1") (pinfunction "Rx_1") (pintype "unspecified"))
      (node (ref "MUX_RX") (pin "3") (pinfunction "B2_3") (pintype "unspecified"))
    )
    (net (code "35") (name "RX2") (class "Default")
      (node (ref "IR3") (pin "1") (pinfunction "Rx_1") (pintype "unspecified"))
      (node (ref "MUX_RX") (pin "2") (pinfunction "B3_2") (pintype "unspecified"))
    )
    (net (code "36") (name "RX3") (class "Default")
      (node (ref "IR4") (pin "1") (pinfunction "Rx_1") (pintype "unspecified"))
      (node (ref "MUX_RX") (pin "1") (pinfunction "B4_1") (pintype "unspecified"))
    )
    (net (code "37") (name "RX4") (class "Default")
      (node (ref "IR5") (pin "1") (pinfunction "Rx_1") (pintype "unspecified"))
      (node (ref "MUX_RX") (pin "15") (pinfunction "B5_15") (pintype "unspecified"))
    )
    (net (code "38") (name "RX5") (class "Default")
      (node (ref "IR6") (pin "1") (pinfunction "Rx_1") (pintype "unspecified"))
      (node (ref "MUX_RX") (pin "14") (pinfunction "B6_14") (pintype "unspecified"))
    )
    (net (code "39") (name "SC0") (class "Default")
      (node (ref "MUX_I2C") (pin "14") (pinfunction "SC2_14") (pintype "unspecified"))
      (node (ref "TOF1") (pin "2") (pinfunction "SCL_2") (pintype "unspecified"))
    )
    (net (code "40") (name "SC1") (class "Default")
      (node (ref "MUX_I2C") (pin "12") (pinfunction "SC1_12") (pintype "unspecified"))
      (node (ref "TOF2") (pin "2") (pinfunction "SCL_2") (pintype "unspecified"))
    )
    (net (code "41") (name "SC2") (class "Default")
      (node (ref "MUX_I2C") (pin "10") (pinfunction "SC0_10") (pintype "unspecified"))
      (node (ref "TOF3") (pin "2") (pinfunction "SCL_2") (pintype "unspecified"))
    )
    (net (code "42") (name "SC3") (class "Default")
      (node (ref "MUX_I2C") (pin "20") (pinfunction "SC5_20") (pintype "unspecified"))
      (node (ref "TOF4") (pin "2") (pinfunction "SCL_2") (pintype "unspecified"))
    )
    (net (code "43") (name "SC4") (class "Default")
      (node (ref "MUX_I2C") (pin "18") (pinfunction "SC4_18") (pintype "unspecified"))
      (node (ref "TOF5") (pin "2") (pinfunction "SCL_2") (pintype "unspecified"))
    )
    (net (code "44") (name "SC5") (class "Default")
      (node (ref "MUX_I2C") (pin "16") (pinfunction "SC3_16") (pintype "unspecified"))
      (node (ref "TOF6") (pin "2") (pinfunction "SCL_2") (pintype "unspecified"))
    )
    (net (code "45") (name "SCL") (class "Default")
      (node (ref "ESP32") (pin "19") (pinfunction "IO11_19") (pintype "unspecified"))
      (node (ref "MUX_I2C") (pin "4") (pinfunction "SCL_4") (pintype "unspecified"))
    )
    (net (code "46") (name "SD0") (class "Default")
      (node (ref "MUX_I2C") (pin "13") (pinfunction "SD2_13") (pintype "unspecified"))
      (node (ref "TOF1") (pin "1") (pinfunction "SDA_1") (pintype "unspecified"))
    )
    (net (code "47") (name "SD1") (class "Default")
      (node (ref "MUX_I2C") (pin "11") (pinfunction "SD1_11") (pintype "unspecified"))
      (node (ref "TOF2") (pin "1") (pinfunction "SDA_1") (pintype "unspecified"))
    )
    (net (code "48") (name "SD2") (class "Default")
      (node (ref "MUX_I2C") (pin "9") (pinfunction "SD0_9") (pintype "unspecified"))
      (node (ref "TOF3") (pin "1") (pinfunction "SDA_1") (pintype "unspecified"))
    )
    (net (code "49") (name "SD3") (class "Default")
      (node (ref "MUX_I2C") (pin "19") (pinfunction "SD5_19") (pintype "unspecified"))
      (node (ref "TOF4") (pin "1") (pinfunction "SDA_1") (pintype "unspecified"))
    )
    (net (code "50") (name "SD4") (class "Default")
      (node (ref "MUX_I2C") (pin "17") (pinfunction "SD4_17") (pintype "unspecified"))
      (node (ref "TOF5") (pin "1") (pinfunction "SDA_1") (pintype "unspecified"))
    )
    (net (code "51") (name "SD5") (class "Default")
      (node (ref "MUX_I2C") (pin "15") (pinfunction "SD3_15") (pintype "unspecified"))
      (node (ref "TOF6") (pin "1") (pinfunction "SDA_1") (pintype "unspecified"))
    )
    (net (code "52") (name "SDA") (class "Default")
      (node (ref "ESP32") (pin "18") (pinfunction "IO10_18") (pintype "unspecified"))
      (node (ref "MUX_I2C") (pin "3") (pinfunction "SDA_3") (pintype "unspecified"))
    )
    (net (code "53") (name "Step1") (class "Default")
      (node (ref "ESP32") (pin "5") (pinfunction "IO5_5") (pintype "unspecified"))
      (node (ref "S1") (pin "2") (pinfunction "STEP_2") (pintype "unspecified"))
    )
    (net (code "54") (name "Step2") (class "Default")
      (node (ref "ESP32") (pin "6") (pinfunction "IO6_6") (pintype "unspecified"))
      (node (ref "S2") (pin "2") (pinfunction "STEP_2") (pintype "unspecified"))
    )
    (net (code "55") (name "Step3") (class "Default")
      (node (ref "ESP32") (pin "7") (pinfunction "IO7_7") (pintype "unspecified"))
      (node (ref "S3") (pin "2") (pinfunction "STEP_2") (pintype "unspecified"))
    )
    (net (code "56") (name "TX0") (class "Default")
      (node (ref "IR1") (pin "2") (pinfunction "Tx_2") (pintype "unspecified"))
      (node (ref "R1") (pin "1") (pinfunction "1_1") (pintype "unspecified"))
    )
    (net (code "57") (name "TX1") (class "Default")
      (node (ref "IR2") (pin "2") (pinfunction "Tx_2") (pintype "unspecified"))
      (node (ref "R2") (pin "2") (pinfunction "2_2") (pintype "unspecified"))
    )
    (net (code "58") (name "TX2") (class "Default")
      (node (ref "IR3") (pin "2") (pinfunction "Tx_2") (pintype "unspecified"))
      (node (ref "R3") (pin "2") (pinfunction "2_2") (pintype "unspecified"))
    )
    (net (code "59") (name "TX3") (class "Default")
      (node (ref "IR4") (pin "2") (pinfunction "Tx_2") (pintype "unspecified"))
      (node (ref "R4") (pin "2") (pinfunction "2_2") (pintype "unspecified"))
    )
    (net (code "60") (name "TX4") (class "Default")
      (node (ref "IR5") (pin "2") (pinfunction "Tx_2") (pintype "unspecified"))
      (node (ref "R5") (pin "2") (pinfunction "2_2") (pintype "unspecified"))
    )
    (net (code "61") (name "TX5") (class "Default")
      (node (ref "IR6") (pin "2") (pinfunction "Tx_2") (pintype "unspecified"))
      (node (ref "R6") (pin "1") (pinfunction "1_1") (pintype "unspecified"))
    )
    (net (code "62") (name "U0RXD") (class "Default")
      (node (ref "ESP32") (pin "36") (pinfunction "RXD0_36") (pintype "unspecified"))
      (node (ref "USB2UART") (pin "26") (pinfunction "TXD_26") (pintype "unspecified"))
    )
    (net (code "63") (name "U0TXD") (class "Default")
      (node (ref "ESP32") (pin "37") (pinfunction "TXD0_37") (pintype "unspecified"))
      (node (ref "USB2UART") (pin "25") (pinfunction "RXD_25") (pintype "unspecified"))
    )
    (net (code "64") (name "USB_D+") (class "Default")
      (node (ref "TVS1") (pin "2") (pinfunction "2_2") (pintype "unspecified"))
      (node (ref "USB") (pin "3") (pinfunction "D+_3") (pintype "unspecified"))
      (node (ref "USB2UART") (pin "4") (pinfunction "D+_4") (pintype "unspecified"))
    )
    (net (code "65") (name "USB_D-") (class "Default")
      (node (ref "TVS2") (pin "2") (pinfunction "2_2") (pintype "unspecified"))
      (node (ref "USB") (pin "2") (pinfunction "D-_2") (pintype "unspecified"))
      (node (ref "USB2UART") (pin "5") (pinfunction "D-_5") (pintype "unspecified"))
    )
    (net (code "66") (name "VBUS") (class "Default")
      (node (ref "D1") (pin "2") (pinfunction "A_2") (pintype "unspecified"))
      (node (ref "R1VBUS") (pin "1") (pinfunction "1_1") (pintype "unspecified"))
      (node (ref "TVS3") (pin "2") (pinfunction "2_2") (pintype "unspecified"))
      (node (ref "USB") (pin "1") (pinfunction "VBUS_1") (pintype "unspecified"))
    )
    (net (code "67") (name "VCC_5V") (class "Default")
      (node (ref "COUT_B1") (pin "2") (pinfunction "2_2") (pintype "unspecified"))
      (node (ref "COUT_B2") (pin "2") (pinfunction "2_2") (pintype "unspecified"))
      (node (ref "COUT_B3") (pin "2") (pinfunction "2_2") (pintype "unspecified"))
      (node (ref "C_PWR_3") (pin "2") (pinfunction "2_2") (pintype "unspecified"))
      (node (ref "C_PWR_4") (pin "2") (pinfunction "2_2") (pintype "unspecified"))
      (node (ref "C_USB") (pin "2") (pinfunction "2_2") (pintype "unspecified"))
      (node (ref "D1") (pin "1") (pinfunction "K_1") (pintype "unspecified"))
      (node (ref "LDO") (pin "3") (pinfunction "VIN_3") (pintype "unspecified"))
      (node (ref "L_BUCK") (pin "2") (pinfunction "2_2") (pintype "unspecified"))
      (node (ref "R_B_FBCK2") (pin "1") (pinfunction "1_1") (pintype "unspecified"))
      (node (ref "TVS4") (pin "1") (pinfunction "K_1") (pintype "unspecified"))
    )
    (net (code "68") (name "VIN") (class "Default")
      (node (ref "BUCK") (pin "7") (pinfunction "VIN_7") (pintype "unspecified"))
      (node (ref "CIN_B1") (pin "2") (pinfunction "2_2") (pintype "unspecified"))
      (node (ref "CIN_B2") (pin "2") (pinfunction "2_2") (pintype "unspecified"))
      (node (ref "CIN_B3") (pin "2") (pinfunction "2_2") (pintype "unspecified"))
      (node (ref "PW") (pin "1") (pinfunction "M+_1") (pintype "unspecified"))
      (node (ref "R_B_EN2") (pin "2") (pinfunction "2_2") (pintype "unspecified"))
    )
    (net (code "69") (name "extraPin1") (class "Default")
      (node (ref "ESP32") (pin "20") (pinfunction "IO12_20") (pintype "unspecified"))
      (node (ref "EXTRAPINS") (pin "1") (pinfunction "1_1") (pintype "unspecified"))
    )
    (net (code "70") (name "extraPin2") (class "Default")
      (node (ref "ESP32") (pin "21") (pinfunction "IO13_21") (pintype "unspecified"))
      (node (ref "EXTRAPINS") (pin "2") (pinfunction "2_2") (pintype "unspecified"))
    )
    (net (code "71") (name "extraPin3") (class "Default")
      (node (ref "ESP32") (pin "22") (pinfunction "IO14_22") (pintype "unspecified"))
      (node (ref "EXTRAPINS") (pin "3") (pinfunction "3_3") (pintype "unspecified"))
    )
    (net (code "72") (name "extraPin4") (class "Default")
      (node (ref "ESP32") (pin "23") (pinfunction "IO21_23") (pintype "unspecified"))
      (node (ref "EXTRAPINS") (pin "4") (pinfunction "4_4") (pintype "unspecified"))
    )
    (net (code "73") (name "unconnected-(BOOT_SW-Pad1)") (class "Default")
      (node (ref "BOOT_SW") (pin "1") (pinfunction "1_1") (pintype "unspecified+no_connect"))
    )
    (net (code "74") (name "unconnected-(BOOT_SW-Pad4)") (class "Default")
      (node (ref "BOOT_SW") (pin "4") (pinfunction "4_4") (pintype "unspecified+no_connect"))
    )
    (net (code "75") (name "unconnected-(ESP32-IO1-Pad39)") (class "Default")
      (node (ref "ESP32") (pin "39") (pinfunction "IO1_39") (pintype "unspecified+no_connect"))
    )
    (net (code "76") (name "unconnected-(ESP32-IO2-Pad38)") (class "Default")
      (node (ref "ESP32") (pin "38") (pinfunction "IO2_38") (pintype "unspecified+no_connect"))
    )
    (net (code "77") (name "unconnected-(ESP32-IO3-Pad15)") (class "Default")
      (node (ref "ESP32") (pin "15") (pinfunction "IO3_15") (pintype "unspecified+no_connect"))
    )
    (net (code "78") (name "unconnected-(ESP32-IO4-Pad4)") (class "Default")
      (node (ref "ESP32") (pin "4") (pinfunction "IO4_4") (pintype "unspecified+no_connect"))
    )
    (net (code "79") (name "unconnected-(ESP32-IO8-Pad12)") (class "Default")
      (node (ref "ESP32") (pin "12") (pinfunction "IO8_12") (pintype "unspecified+no_connect"))
    )
    (net (code "80") (name "unconnected-(ESP32-IO15-Pad8)") (class "Default")
      (node (ref "ESP32") (pin "8") (pinfunction "IO15_8") (pintype "unspecified+no_connect"))
    )
    (net (code "81") (name "unconnected-(ESP32-IO19-Pad13)") (class "Default")
      (node (ref "ESP32") (pin "13") (pinfunction "IO19_13") (pintype "unspecified+no_connect"))
    )
    (net (code "82") (name "unconnected-(ESP32-IO20-Pad14)") (class "Default")
      (node (ref "ESP32") (pin "14") (pinfunction "IO20_14") (pintype "unspecified+no_connect"))
    )
    (net (code "83") (name "unconnected-(ESP32-IO40-Pad33)") (class "Default")
      (node (ref "ESP32") (pin "33") (pinfunction "IO40_33") (pintype "unspecified+no_connect"))
    )
    (net (code "84") (name "unconnected-(ESP32-IO41-Pad34)") (class "Default")
      (node (ref "ESP32") (pin "34") (pinfunction "IO41_34") (pintype "unspecified+no_connect"))
    )
    (net (code "85") (name "unconnected-(ESP32-IO42-Pad35)") (class "Default")
      (node (ref "ESP32") (pin "35") (pinfunction "IO42_35") (pintype "unspecified+no_connect"))
    )
    (net (code "86") (name "unconnected-(ESP32-IO45-Pad26)") (class "Default")
      (node (ref "ESP32") (pin "26") (pinfunction "IO45_26") (pintype "unspecified+no_connect"))
    )
    (net (code "87") (name "unconnected-(ESP32-IO46-Pad16)") (class "Default")
      (node (ref "ESP32") (pin "16") (pinfunction "IO46_16") (pintype "unspecified+no_connect"))
    )
    (net (code "88") (name "unconnected-(ESP32-IO47-Pad24)") (class "Default")
      (node (ref "ESP32") (pin "24") (pinfunction "IO47_24") (pintype "unspecified+no_connect"))
    )
    (net (code "89") (name "unconnected-(ESP32-IO48-Pad25)") (class "Default")
      (node (ref "ESP32") (pin "25") (pinfunction "IO48_25") (pintype "unspecified+no_connect"))
    )
    (net (code "90") (name "unconnected-(IRLEDREF-A-Pad1)") (class "Default")
      (node (ref "IRLEDREF") (pin "1") (pinfunction "A_1") (pintype "input+no_connect"))
    )
    (net (code "91") (name "unconnected-(IRRECREF-OUT-Pad1)") (class "Default")
      (node (ref "IRRECREF") (pin "1") (pinfunction "OUT_1") (pintype "unspecified+no_connect"))
    )
    (net (code "92") (name "unconnected-(IRRECREF-VS-Pad3)") (class "Default")
      (node (ref "IRRECREF") (pin "3") (pinfunction "VS_3") (pintype "unspecified+no_connect"))
    )
    (net (code "93") (name "unconnected-(MUX_I2C-SC6-Pad22)") (class "Default")
      (node (ref "MUX_I2C") (pin "22") (pinfunction "SC6_22") (pintype "unspecified+no_connect"))
    )
    (net (code "94") (name "unconnected-(MUX_I2C-SC7-Pad24)") (class "Default")
      (node (ref "MUX_I2C") (pin "24") (pinfunction "SC7_24") (pintype "unspecified+no_connect"))
    )
    (net (code "95") (name "unconnected-(MUX_I2C-SD6-Pad21)") (class "Default")
      (node (ref "MUX_I2C") (pin "21") (pinfunction "SD6_21") (pintype "unspecified+no_connect"))
    )
    (net (code "96") (name "unconnected-(MUX_I2C-SD7-Pad23)") (class "Default")
      (node (ref "MUX_I2C") (pin "23") (pinfunction "SD7_23") (pintype "unspecified+no_connect"))
    )
    (net (code "97") (name "unconnected-(MUX_RX-B7-Pad13)") (class "Default")
      (node (ref "MUX_RX") (pin "13") (pinfunction "B7_13") (pintype "unspecified+no_connect"))
    )
    (net (code "98") (name "unconnected-(MUX_RX-B8-Pad12)") (class "Default")
      (node (ref "MUX_RX") (pin "12") (pinfunction "B8_12") (pintype "unspecified+no_connect"))
    )
    (net (code "99") (name "unconnected-(MUX_RX-NC-Pad6)") (class "Default")
      (node (ref "MUX_RX") (pin "6") (pinfunction "NC_6") (pintype "unspecified+no_connect"))
    )
    (net (code "100") (name "unconnected-(MUX_TX-B7-Pad13)") (class "Default")
      (node (ref "MUX_TX") (pin "13") (pinfunction "B7_13") (pintype "unspecified+no_connect"))
    )
    (net (code "101") (name "unconnected-(MUX_TX-B8-Pad12)") (class "Default")
      (node (ref "MUX_TX") (pin "12") (pinfunction "B8_12") (pintype "unspecified+no_connect"))
    )
    (net (code "102") (name "unconnected-(MUX_TX-NC-Pad6)") (class "Default")
      (node (ref "MUX_TX") (pin "6") (pinfunction "NC_6") (pintype "unspecified+no_connect"))
    )
    (net (code "103") (name "unconnected-(RGB-DOUT-Pad3)") (class "Default")
      (node (ref "RGB") (pin "3") (pinfunction "DOUT_3") (pintype "unspecified+no_connect"))
    )
    (net (code "104") (name "unconnected-(RST_SW-Pad2)") (class "Default")
      (node (ref "RST_SW") (pin "2") (pinfunction "2_2") (pintype "unspecified+no_connect"))
    )
    (net (code "105") (name "unconnected-(RST_SW-Pad3)") (class "Default")
      (node (ref "RST_SW") (pin "3") (pinfunction "3_3") (pintype "unspecified+no_connect"))
    )
    (net (code "106") (name "unconnected-(TOF_REF-GND-Pad2)") (class "Default")
      (node (ref "TOF_REF") (pin "2") (pinfunction "GND_2") (pintype "unspecified+no_connect"))
    )
    (net (code "107") (name "unconnected-(TOF_REF-GPIO1-Pad5)") (class "Default")
      (node (ref "TOF_REF") (pin "5") (pinfunction "GPIO1_5") (pintype "unspecified+no_connect"))
    )
    (net (code "108") (name "unconnected-(TOF_REF-SCL-Pad3)") (class "Default")
      (node (ref "TOF_REF") (pin "3") (pinfunction "SCL_3") (pintype "unspecified+no_connect"))
    )
    (net (code "109") (name "unconnected-(TOF_REF-SDA-Pad4)") (class "Default")
      (node (ref "TOF_REF") (pin "4") (pinfunction "SDA_4") (pintype "unspecified+no_connect"))
    )
    (net (code "110") (name "unconnected-(TOF_REF-VIN-Pad1)") (class "Default")
      (node (ref "TOF_REF") (pin "1") (pinfunction "VIN_1") (pintype "unspecified+no_connect"))
    )
    (net (code "111") (name "unconnected-(TOF_REF-XSHUT-Pad6)") (class "Default")
      (node (ref "TOF_REF") (pin "6") (pinfunction "XSHUT_6") (pintype "unspecified+no_connect"))
    )
    (net (code "112") (name "unconnected-(U7-1A-Pad12)") (class "Default")
      (node (ref "U7") (pin "12") (pinfunction "1A_12") (pintype "unspecified+no_connect"))
    )
    (net (code "113") (name "unconnected-(U7-1B-Pad11)") (class "Default")
      (node (ref "U7") (pin "11") (pinfunction "1B_11") (pintype "unspecified+no_connect"))
    )
    (net (code "114") (name "unconnected-(U7-2A-Pad13)") (class "Default")
      (node (ref "U7") (pin "13") (pinfunction "2A_13") (pintype "unspecified+no_connect"))
    )
    (net (code "115") (name "unconnected-(U7-2B-Pad14)") (class "Default")
      (node (ref "U7") (pin "14") (pinfunction "2B_14") (pintype "unspecified+no_connect"))
    )
    (net (code "116") (name "unconnected-(U7-DIR-Pad8)") (class "Default")
      (node (ref "U7") (pin "8") (pinfunction "DIR_8") (pintype "unspecified+no_connect"))
    )
    (net (code "117") (name "unconnected-(U7-EN#-Pad1)") (class "Default")
      (node (ref "U7") (pin "1") (pinfunction "EN#_1") (pintype "unspecified+no_connect"))
    )
    (net (code "118") (name "unconnected-(U7-GND-Pad9)") (class "Default")
      (node (ref "U7") (pin "9") (pinfunction "GND_9") (pintype "unspecified+no_connect"))
    )
    (net (code "119") (name "unconnected-(U7-GND-Pad15)") (class "Default")
      (node (ref "U7") (pin "15") (pinfunction "GND_15") (pintype "unspecified+no_connect"))
    )
    (net (code "120") (name "unconnected-(U7-MS1-Pad2)") (class "Default")
      (node (ref "U7") (pin "2") (pinfunction "MS1_2") (pintype "unspecified+no_connect"))
    )
    (net (code "121") (name "unconnected-(U7-MS2-Pad3)") (class "Default")
      (node (ref "U7") (pin "3") (pinfunction "MS2_3") (pintype "unspecified+no_connect"))
    )
    (net (code "122") (name "unconnected-(U7-MS3-Pad4)") (class "Default")
      (node (ref "U7") (pin "4") (pinfunction "MS3_4") (pintype "unspecified+no_connect"))
    )
    (net (code "123") (name "unconnected-(U7-RST#-Pad5)") (class "Default")
      (node (ref "U7") (pin "5") (pinfunction "RST#_5") (pintype "unspecified+no_connect"))
    )
    (net (code "124") (name "unconnected-(U7-SLP#-Pad6)") (class "Default")
      (node (ref "U7") (pin "6") (pinfunction "SLP#_6") (pintype "unspecified+no_connect"))
    )
    (net (code "125") (name "unconnected-(U7-STEP-Pad7)") (class "Default")
      (node (ref "U7") (pin "7") (pinfunction "STEP_7") (pintype "unspecified+no_connect"))
    )
    (net (code "126") (name "unconnected-(U7-VDD-Pad10)") (class "Default")
      (node (ref "U7") (pin "10") (pinfunction "VDD_10") (pintype "unspecified+no_connect"))
    )
    (net (code "127") (name "unconnected-(U7-VMOT-Pad16)") (class "Default")
      (node (ref "U7") (pin "16") (pinfunction "VMOT_16") (pintype "unspecified+no_connect"))
    )
    (net (code "128") (name "unconnected-(USB-EP-Pad6)") (class "Default")
      (node (ref "USB") (pin "6") (pinfunction "EP_6") (pintype "unspecified+no_connect"))
    )
    (net (code "129") (name "unconnected-(USB-EP-Pad7)") (class "Default")
      (node (ref "USB") (pin "7") (pinfunction "EP_7") (pintype "unspecified+no_connect"))
    )
    (net (code "130") (name "unconnected-(USB-EP-Pad8)") (class "Default")
      (node (ref "USB") (pin "8") (pinfunction "EP_8") (pintype "unspecified+no_connect"))
    )
    (net (code "131") (name "unconnected-(USB-EP-Pad9)") (class "Default")
      (node (ref "USB") (pin "9") (pinfunction "EP_9") (pintype "unspecified+no_connect"))
    )
    (net (code "132") (name "unconnected-(USB-ID-Pad4)") (class "Default")
      (node (ref "USB") (pin "4") (pinfunction "ID_4") (pintype "unspecified+no_connect"))
    )
    (net (code "133") (name "unconnected-(USB2UART-CHR0-Pad15)") (class "Default")
      (node (ref "USB2UART") (pin "15") (pinfunction "CHR0_15") (pintype "unspecified+no_connect"))
    )
    (net (code "134") (name "unconnected-(USB2UART-CHR1-Pad14)") (class "Default")
      (node (ref "USB2UART") (pin "14") (pinfunction "CHR1_14") (pintype "unspecified+no_connect"))
    )
    (net (code "135") (name "unconnected-(USB2UART-CHREN-Pad13)") (class "Default")
      (node (ref "USB2UART") (pin "13") (pinfunction "CHREN_13") (pintype "unspecified+no_connect"))
    )
    (net (code "136") (name "unconnected-(USB2UART-CTS-Pad23)") (class "Default")
      (node (ref "USB2UART") (pin "23") (pinfunction "CTS_23") (pintype "unspecified+no_connect"))
    )
    (net (code "137") (name "unconnected-(USB2UART-DCD-Pad1)") (class "Default")
      (node (ref "USB2UART") (pin "1") (pinfunction "DCD_1") (pintype "unspecified+no_connect"))
    )
    (net (code "138") (name "unconnected-(USB2UART-DSR-Pad27)") (class "Default")
      (node (ref "USB2UART") (pin "27") (pinfunction "DSR_27") (pintype "unspecified+no_connect"))
    )
    (net (code "139") (name "unconnected-(USB2UART-DTR-Pad28)") (class "Default")
      (node (ref "USB2UART") (pin "28") (pinfunction "DTR_28") (pintype "unspecified+no_connect"))
    )
    (net (code "140") (name "unconnected-(USB2UART-GPIO.0{slash}TXT-Pad19)") (class "Default")
      (node (ref "USB2UART") (pin "19") (pinfunction "GPIO.0/TXT_19") (pintype "unspecified+no_connect"))
    )
    (net (code "141") (name "unconnected-(USB2UART-GPIO.1{slash}RXT-Pad18)") (class "Default")
      (node (ref "USB2UART") (pin "18") (pinfunction "GPIO.1/RXT_18") (pintype "unspecified+no_connect"))
    )
    (net (code "142") (name "unconnected-(USB2UART-GPIO.2{slash}RS485-Pad17)") (class "Default")
      (node (ref "USB2UART") (pin "17") (pinfunction "GPIO.2/RS485_17") (pintype "unspecified+no_connect"))
    )
    (net (code "143") (name "unconnected-(USB2UART-GPIO.3{slash}WAKEUP-Pad16)") (class "Default")
      (node (ref "USB2UART") (pin "16") (pinfunction "GPIO.3/WAKEUP_16") (pintype "unspecified+no_connect"))
    )
    (net (code "144") (name "unconnected-(USB2UART-GPIO.4-Pad22)") (class "Default")
      (node (ref "USB2UART") (pin "22") (pinfunction "GPIO.4_22") (pintype "unspecified+no_connect"))
    )
    (net (code "145") (name "unconnected-(USB2UART-GPIO.5-Pad21)") (class "Default")
      (node (ref "USB2UART") (pin "21") (pinfunction "GPIO.5_21") (pintype "unspecified+no_connect"))
    )
    (net (code "146") (name "unconnected-(USB2UART-GPIO.6-Pad20)") (class "Default")
      (node (ref "USB2UART") (pin "20") (pinfunction "GPIO.6_20") (pintype "unspecified+no_connect"))
    )
    (net (code "147") (name "unconnected-(USB2UART-NC-Pad10)") (class "Default")
      (node (ref "USB2UART") (pin "10") (pinfunction "NC_10") (pintype "unspecified+no_connect"))
    )
    (net (code "148") (name "unconnected-(USB2UART-RI{slash}CLK-Pad2)") (class "Default")
      (node (ref "USB2UART") (pin "2") (pinfunction "RI/CLK_2") (pintype "unspecified+no_connect"))
    )
    (net (code "149") (name "unconnected-(USB2UART-RTS-Pad24)") (class "Default")
      (node (ref "USB2UART") (pin "24") (pinfunction "RTS_24") (pintype "unspecified+no_connect"))
    )
    (net (code "150") (name "unconnected-(USB2UART-SUSPEND-Pad12)") (class "Default")
      (node (ref "USB2UART") (pin "12") (pinfunction "SUSPEND_12") (pintype "unspecified+no_connect"))
    )
    (net (code "151") (name "unconnected-(USB2UART-SUSPENDb-Pad11)") (class "Default")
      (node (ref "USB2UART") (pin "11") (pinfunction "SUSPENDb_11") (pintype "unspecified+no_connect"))
    )
  )
)
